# Wii_U_display_tap.net
KiCad netlist of a schematic drawn in EAGLE
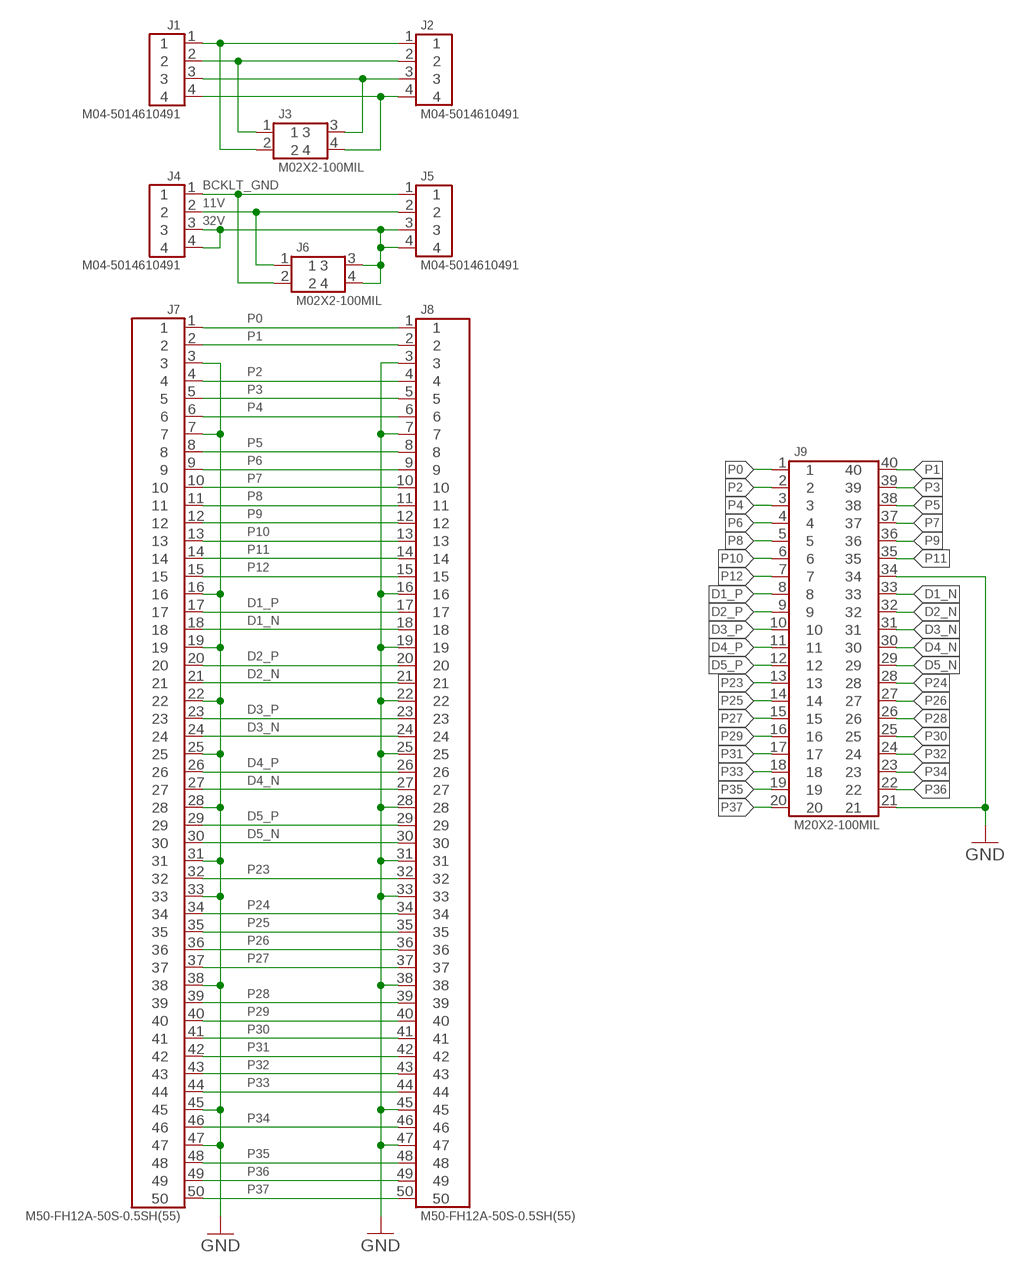
[diagram p0: schematic, sheet 1]

(export (version "E")
  (design (tool "Eeschema 10.0.6"))
  (components
    (comp (ref "J1")
      (value "M04-5014610491")
      (footprint "eagle-import:5014610491")
      (libsource (lib "eagle-import") (part "M04-5014610491"))
    )
    (comp (ref "J2")
      (value "M04-5014610491")
      (footprint "eagle-import:5014610491")
      (libsource (lib "eagle-import") (part "M04-5014610491"))
    )
    (comp (ref "J3")
      (value "M02X2-100MIL")
      (footprint "eagle-import:M02X2-100MIL")
      (libsource (lib "eagle-import") (part "M02X2-100MIL"))
    )
    (comp (ref "J4")
      (value "M04-5014610491")
      (footprint "eagle-import:5014610491")
      (libsource (lib "eagle-import") (part "M04-5014610491"))
    )
    (comp (ref "J5")
      (value "M04-5014610491")
      (footprint "eagle-import:5014610491")
      (libsource (lib "eagle-import") (part "M04-5014610491"))
    )
    (comp (ref "J6")
      (value "M02X2-100MIL")
      (footprint "eagle-import:M02X2-100MIL")
      (libsource (lib "eagle-import") (part "M02X2-100MIL"))
    )
    (comp (ref "J7")
      (value "M50-FH12A-50S-0.5SH(55)")
      (footprint "eagle-import:FH12A-50S-0.5SH(55)")
      (libsource (lib "eagle-import") (part "M50-FH12A-50S-0.5SH(55)"))
    )
    (comp (ref "J8")
      (value "M50-FH12A-50S-0.5SH(55)")
      (footprint "eagle-import:FH12A-50S-0.5SH(55)")
      (libsource (lib "eagle-import") (part "M50-FH12A-50S-0.5SH(55)"))
    )
    (comp (ref "J9")
      (value "M20X2-100MIL")
      (footprint "eagle-import:M20X2-100MIL")
      (libsource (lib "eagle-import") (part "M20X2-100MIL"))
    )
  )
  (nets
    (net (code "1") (name "/11V") (class "Default")
      (node (ref "J4") (pin "2") (pinfunction "2_2") (pintype "bidirectional"))
      (node (ref "J5") (pin "2") (pinfunction "2_2") (pintype "bidirectional"))
      (node (ref "J6") (pin "1") (pinfunction "1_1") (pintype "bidirectional"))
    )
    (net (code "2") (name "/32V") (class "Default")
      (node (ref "J4") (pin "3") (pinfunction "3_3") (pintype "bidirectional"))
      (node (ref "J4") (pin "4") (pinfunction "4_4") (pintype "bidirectional"))
      (node (ref "J5") (pin "3") (pinfunction "3_3") (pintype "bidirectional"))
      (node (ref "J5") (pin "4") (pinfunction "4_4") (pintype "bidirectional"))
      (node (ref "J6") (pin "3") (pinfunction "3_3") (pintype "bidirectional"))
      (node (ref "J6") (pin "4") (pinfunction "4_4") (pintype "bidirectional"))
    )
    (net (code "3") (name "/BCKLT_GND") (class "Default")
      (node (ref "J4") (pin "1") (pinfunction "1_1") (pintype "bidirectional"))
      (node (ref "J5") (pin "1") (pinfunction "1_1") (pintype "bidirectional"))
      (node (ref "J6") (pin "2") (pinfunction "2_2") (pintype "bidirectional"))
    )
    (net (code "4") (name "D1_N") (class "Default")
      (node (ref "J7") (pin "18") (pinfunction "18_18") (pintype "bidirectional"))
      (node (ref "J8") (pin "18") (pinfunction "18_18") (pintype "bidirectional"))
      (node (ref "J9") (pin "33") (pinfunction "33_33") (pintype "bidirectional"))
    )
    (net (code "5") (name "D1_P") (class "Default")
      (node (ref "J7") (pin "17") (pinfunction "17_17") (pintype "bidirectional"))
      (node (ref "J8") (pin "17") (pinfunction "17_17") (pintype "bidirectional"))
      (node (ref "J9") (pin "8") (pinfunction "8_8") (pintype "bidirectional"))
    )
    (net (code "6") (name "D2_N") (class "Default")
      (node (ref "J7") (pin "21") (pinfunction "21_21") (pintype "bidirectional"))
      (node (ref "J8") (pin "21") (pinfunction "21_21") (pintype "bidirectional"))
      (node (ref "J9") (pin "32") (pinfunction "32_32") (pintype "bidirectional"))
    )
    (net (code "7") (name "D2_P") (class "Default")
      (node (ref "J7") (pin "20") (pinfunction "20_20") (pintype "bidirectional"))
      (node (ref "J8") (pin "20") (pinfunction "20_20") (pintype "bidirectional"))
      (node (ref "J9") (pin "9") (pinfunction "9_9") (pintype "bidirectional"))
    )
    (net (code "8") (name "D3_N") (class "Default")
      (node (ref "J7") (pin "24") (pinfunction "24_24") (pintype "bidirectional"))
      (node (ref "J8") (pin "24") (pinfunction "24_24") (pintype "bidirectional"))
      (node (ref "J9") (pin "31") (pinfunction "31_31") (pintype "bidirectional"))
    )
    (net (code "9") (name "D3_P") (class "Default")
      (node (ref "J7") (pin "23") (pinfunction "23_23") (pintype "bidirectional"))
      (node (ref "J8") (pin "23") (pinfunction "23_23") (pintype "bidirectional"))
      (node (ref "J9") (pin "10") (pinfunction "10_10") (pintype "bidirectional"))
    )
    (net (code "10") (name "D4_N") (class "Default")
      (node (ref "J7") (pin "27") (pinfunction "27_27") (pintype "bidirectional"))
      (node (ref "J8") (pin "27") (pinfunction "27_27") (pintype "bidirectional"))
      (node (ref "J9") (pin "30") (pinfunction "30_30") (pintype "bidirectional"))
    )
    (net (code "11") (name "D4_P") (class "Default")
      (node (ref "J7") (pin "26") (pinfunction "26_26") (pintype "bidirectional"))
      (node (ref "J8") (pin "26") (pinfunction "26_26") (pintype "bidirectional"))
      (node (ref "J9") (pin "11") (pinfunction "11_11") (pintype "bidirectional"))
    )
    (net (code "12") (name "D5_N") (class "Default")
      (node (ref "J7") (pin "30") (pinfunction "30_30") (pintype "bidirectional"))
      (node (ref "J8") (pin "30") (pinfunction "30_30") (pintype "bidirectional"))
      (node (ref "J9") (pin "29") (pinfunction "29_29") (pintype "bidirectional"))
    )
    (net (code "13") (name "D5_P") (class "Default")
      (node (ref "J7") (pin "29") (pinfunction "29_29") (pintype "bidirectional"))
      (node (ref "J8") (pin "29") (pinfunction "29_29") (pintype "bidirectional"))
      (node (ref "J9") (pin "12") (pinfunction "12_12") (pintype "bidirectional"))
    )
    (net (code "14") (name "GND") (class "Default")
      (node (ref "J7") (pin "16") (pinfunction "16_16") (pintype "bidirectional"))
      (node (ref "J7") (pin "19") (pinfunction "19_19") (pintype "bidirectional"))
      (node (ref "J7") (pin "22") (pinfunction "22_22") (pintype "bidirectional"))
      (node (ref "J7") (pin "25") (pinfunction "25_25") (pintype "bidirectional"))
      (node (ref "J7") (pin "28") (pinfunction "28_28") (pintype "bidirectional"))
      (node (ref "J7") (pin "3") (pinfunction "3_3") (pintype "bidirectional"))
      (node (ref "J7") (pin "31") (pinfunction "31_31") (pintype "bidirectional"))
      (node (ref "J7") (pin "33") (pinfunction "33_33") (pintype "bidirectional"))
      (node (ref "J7") (pin "38") (pinfunction "38_38") (pintype "bidirectional"))
      (node (ref "J7") (pin "45") (pinfunction "45_45") (pintype "bidirectional"))
      (node (ref "J7") (pin "47") (pinfunction "47_47") (pintype "bidirectional"))
      (node (ref "J7") (pin "7") (pinfunction "7_7") (pintype "bidirectional"))
      (node (ref "J8") (pin "16") (pinfunction "16_16") (pintype "bidirectional"))
      (node (ref "J8") (pin "19") (pinfunction "19_19") (pintype "bidirectional"))
      (node (ref "J8") (pin "22") (pinfunction "22_22") (pintype "bidirectional"))
      (node (ref "J8") (pin "25") (pinfunction "25_25") (pintype "bidirectional"))
      (node (ref "J8") (pin "28") (pinfunction "28_28") (pintype "bidirectional"))
      (node (ref "J8") (pin "3") (pinfunction "3_3") (pintype "bidirectional"))
      (node (ref "J8") (pin "31") (pinfunction "31_31") (pintype "bidirectional"))
      (node (ref "J8") (pin "33") (pinfunction "33_33") (pintype "bidirectional"))
      (node (ref "J8") (pin "38") (pinfunction "38_38") (pintype "bidirectional"))
      (node (ref "J8") (pin "45") (pinfunction "45_45") (pintype "bidirectional"))
      (node (ref "J8") (pin "47") (pinfunction "47_47") (pintype "bidirectional"))
      (node (ref "J8") (pin "7") (pinfunction "7_7") (pintype "bidirectional"))
      (node (ref "J9") (pin "21") (pinfunction "21_21") (pintype "bidirectional"))
      (node (ref "J9") (pin "34") (pinfunction "34_34") (pintype "bidirectional"))
    )
    (net (code "15") (name "Net-(J1-Pad1)") (class "Default")
      (node (ref "J1") (pin "1") (pinfunction "1_1") (pintype "bidirectional"))
      (node (ref "J2") (pin "1") (pinfunction "1_1") (pintype "bidirectional"))
      (node (ref "J3") (pin "2") (pinfunction "2_2") (pintype "bidirectional"))
    )
    (net (code "16") (name "Net-(J1-Pad2)") (class "Default")
      (node (ref "J1") (pin "2") (pinfunction "2_2") (pintype "bidirectional"))
      (node (ref "J2") (pin "2") (pinfunction "2_2") (pintype "bidirectional"))
      (node (ref "J3") (pin "1") (pinfunction "1_1") (pintype "bidirectional"))
    )
    (net (code "17") (name "Net-(J1-Pad3)") (class "Default")
      (node (ref "J1") (pin "3") (pinfunction "3_3") (pintype "bidirectional"))
      (node (ref "J2") (pin "3") (pinfunction "3_3") (pintype "bidirectional"))
      (node (ref "J3") (pin "3") (pinfunction "3_3") (pintype "bidirectional"))
    )
    (net (code "18") (name "Net-(J1-Pad4)") (class "Default")
      (node (ref "J1") (pin "4") (pinfunction "4_4") (pintype "bidirectional"))
      (node (ref "J2") (pin "4") (pinfunction "4_4") (pintype "bidirectional"))
      (node (ref "J3") (pin "4") (pinfunction "4_4") (pintype "bidirectional"))
    )
    (net (code "19") (name "P0") (class "Default")
      (node (ref "J7") (pin "1") (pinfunction "1_1") (pintype "bidirectional"))
      (node (ref "J8") (pin "1") (pinfunction "1_1") (pintype "bidirectional"))
      (node (ref "J9") (pin "1") (pinfunction "1_1") (pintype "bidirectional"))
    )
    (net (code "20") (name "P1") (class "Default")
      (node (ref "J7") (pin "2") (pinfunction "2_2") (pintype "bidirectional"))
      (node (ref "J8") (pin "2") (pinfunction "2_2") (pintype "bidirectional"))
      (node (ref "J9") (pin "40") (pinfunction "40_40") (pintype "bidirectional"))
    )
    (net (code "21") (name "P2") (class "Default")
      (node (ref "J7") (pin "4") (pinfunction "4_4") (pintype "bidirectional"))
      (node (ref "J8") (pin "4") (pinfunction "4_4") (pintype "bidirectional"))
      (node (ref "J9") (pin "2") (pinfunction "2_2") (pintype "bidirectional"))
    )
    (net (code "22") (name "P3") (class "Default")
      (node (ref "J7") (pin "5") (pinfunction "5_5") (pintype "bidirectional"))
      (node (ref "J8") (pin "5") (pinfunction "5_5") (pintype "bidirectional"))
      (node (ref "J9") (pin "39") (pinfunction "39_39") (pintype "bidirectional"))
    )
    (net (code "23") (name "P4") (class "Default")
      (node (ref "J7") (pin "6") (pinfunction "6_6") (pintype "bidirectional"))
      (node (ref "J8") (pin "6") (pinfunction "6_6") (pintype "bidirectional"))
      (node (ref "J9") (pin "3") (pinfunction "3_3") (pintype "bidirectional"))
    )
    (net (code "24") (name "P5") (class "Default")
      (node (ref "J7") (pin "8") (pinfunction "8_8") (pintype "bidirectional"))
      (node (ref "J8") (pin "8") (pinfunction "8_8") (pintype "bidirectional"))
      (node (ref "J9") (pin "38") (pinfunction "38_38") (pintype "bidirectional"))
    )
    (net (code "25") (name "P6") (class "Default")
      (node (ref "J7") (pin "9") (pinfunction "9_9") (pintype "bidirectional"))
      (node (ref "J8") (pin "9") (pinfunction "9_9") (pintype "bidirectional"))
      (node (ref "J9") (pin "4") (pinfunction "4_4") (pintype "bidirectional"))
    )
    (net (code "26") (name "P7") (class "Default")
      (node (ref "J7") (pin "10") (pinfunction "10_10") (pintype "bidirectional"))
      (node (ref "J8") (pin "10") (pinfunction "10_10") (pintype "bidirectional"))
      (node (ref "J9") (pin "37") (pinfunction "37_37") (pintype "bidirectional"))
    )
    (net (code "27") (name "P8") (class "Default")
      (node (ref "J7") (pin "11") (pinfunction "11_11") (pintype "bidirectional"))
      (node (ref "J8") (pin "11") (pinfunction "11_11") (pintype "bidirectional"))
      (node (ref "J9") (pin "5") (pinfunction "5_5") (pintype "bidirectional"))
    )
    (net (code "28") (name "P9") (class "Default")
      (node (ref "J7") (pin "12") (pinfunction "12_12") (pintype "bidirectional"))
      (node (ref "J8") (pin "12") (pinfunction "12_12") (pintype "bidirectional"))
      (node (ref "J9") (pin "36") (pinfunction "36_36") (pintype "bidirectional"))
    )
    (net (code "29") (name "P10") (class "Default")
      (node (ref "J7") (pin "13") (pinfunction "13_13") (pintype "bidirectional"))
      (node (ref "J8") (pin "13") (pinfunction "13_13") (pintype "bidirectional"))
      (node (ref "J9") (pin "6") (pinfunction "6_6") (pintype "bidirectional"))
    )
    (net (code "30") (name "P11") (class "Default")
      (node (ref "J7") (pin "14") (pinfunction "14_14") (pintype "bidirectional"))
      (node (ref "J8") (pin "14") (pinfunction "14_14") (pintype "bidirectional"))
      (node (ref "J9") (pin "35") (pinfunction "35_35") (pintype "bidirectional"))
    )
    (net (code "31") (name "P12") (class "Default")
      (node (ref "J7") (pin "15") (pinfunction "15_15") (pintype "bidirectional"))
      (node (ref "J8") (pin "15") (pinfunction "15_15") (pintype "bidirectional"))
      (node (ref "J9") (pin "7") (pinfunction "7_7") (pintype "bidirectional"))
    )
    (net (code "32") (name "P23") (class "Default")
      (node (ref "J7") (pin "32") (pinfunction "32_32") (pintype "bidirectional"))
      (node (ref "J8") (pin "32") (pinfunction "32_32") (pintype "bidirectional"))
      (node (ref "J9") (pin "13") (pinfunction "13_13") (pintype "bidirectional"))
    )
    (net (code "33") (name "P24") (class "Default")
      (node (ref "J7") (pin "34") (pinfunction "34_34") (pintype "bidirectional"))
      (node (ref "J8") (pin "34") (pinfunction "34_34") (pintype "bidirectional"))
      (node (ref "J9") (pin "28") (pinfunction "28_28") (pintype "bidirectional"))
    )
    (net (code "34") (name "P25") (class "Default")
      (node (ref "J7") (pin "35") (pinfunction "35_35") (pintype "bidirectional"))
      (node (ref "J8") (pin "35") (pinfunction "35_35") (pintype "bidirectional"))
      (node (ref "J9") (pin "14") (pinfunction "14_14") (pintype "bidirectional"))
    )
    (net (code "35") (name "P26") (class "Default")
      (node (ref "J7") (pin "36") (pinfunction "36_36") (pintype "bidirectional"))
      (node (ref "J8") (pin "36") (pinfunction "36_36") (pintype "bidirectional"))
      (node (ref "J9") (pin "27") (pinfunction "27_27") (pintype "bidirectional"))
    )
    (net (code "36") (name "P27") (class "Default")
      (node (ref "J7") (pin "37") (pinfunction "37_37") (pintype "bidirectional"))
      (node (ref "J8") (pin "37") (pinfunction "37_37") (pintype "bidirectional"))
      (node (ref "J9") (pin "15") (pinfunction "15_15") (pintype "bidirectional"))
    )
    (net (code "37") (name "P28") (class "Default")
      (node (ref "J7") (pin "39") (pinfunction "39_39") (pintype "bidirectional"))
      (node (ref "J8") (pin "39") (pinfunction "39_39") (pintype "bidirectional"))
      (node (ref "J9") (pin "26") (pinfunction "26_26") (pintype "bidirectional"))
    )
    (net (code "38") (name "P29") (class "Default")
      (node (ref "J7") (pin "40") (pinfunction "40_40") (pintype "bidirectional"))
      (node (ref "J8") (pin "40") (pinfunction "40_40") (pintype "bidirectional"))
      (node (ref "J9") (pin "16") (pinfunction "16_16") (pintype "bidirectional"))
    )
    (net (code "39") (name "P30") (class "Default")
      (node (ref "J7") (pin "41") (pinfunction "41_41") (pintype "bidirectional"))
      (node (ref "J8") (pin "41") (pinfunction "41_41") (pintype "bidirectional"))
      (node (ref "J9") (pin "25") (pinfunction "25_25") (pintype "bidirectional"))
    )
    (net (code "40") (name "P31") (class "Default")
      (node (ref "J7") (pin "42") (pinfunction "42_42") (pintype "bidirectional"))
      (node (ref "J8") (pin "42") (pinfunction "42_42") (pintype "bidirectional"))
      (node (ref "J9") (pin "17") (pinfunction "17_17") (pintype "bidirectional"))
    )
    (net (code "41") (name "P32") (class "Default")
      (node (ref "J7") (pin "43") (pinfunction "43_43") (pintype "bidirectional"))
      (node (ref "J8") (pin "43") (pinfunction "43_43") (pintype "bidirectional"))
      (node (ref "J9") (pin "24") (pinfunction "24_24") (pintype "bidirectional"))
    )
    (net (code "42") (name "P33") (class "Default")
      (node (ref "J7") (pin "44") (pinfunction "44_44") (pintype "bidirectional"))
      (node (ref "J8") (pin "44") (pinfunction "44_44") (pintype "bidirectional"))
      (node (ref "J9") (pin "18") (pinfunction "18_18") (pintype "bidirectional"))
    )
    (net (code "43") (name "P34") (class "Default")
      (node (ref "J7") (pin "46") (pinfunction "46_46") (pintype "bidirectional"))
      (node (ref "J8") (pin "46") (pinfunction "46_46") (pintype "bidirectional"))
      (node (ref "J9") (pin "23") (pinfunction "23_23") (pintype "bidirectional"))
    )
    (net (code "44") (name "P35") (class "Default")
      (node (ref "J7") (pin "48") (pinfunction "48_48") (pintype "bidirectional"))
      (node (ref "J8") (pin "48") (pinfunction "48_48") (pintype "bidirectional"))
      (node (ref "J9") (pin "19") (pinfunction "19_19") (pintype "bidirectional"))
    )
    (net (code "45") (name "P36") (class "Default")
      (node (ref "J7") (pin "49") (pinfunction "49_49") (pintype "bidirectional"))
      (node (ref "J8") (pin "49") (pinfunction "49_49") (pintype "bidirectional"))
      (node (ref "J9") (pin "22") (pinfunction "22_22") (pintype "bidirectional"))
    )
    (net (code "46") (name "P37") (class "Default")
      (node (ref "J7") (pin "50") (pinfunction "50_50") (pintype "bidirectional"))
      (node (ref "J8") (pin "50") (pinfunction "50_50") (pintype "bidirectional"))
      (node (ref "J9") (pin "20") (pinfunction "20_20") (pintype "bidirectional"))
    )
  )
)
